# RMXU_V11.net
KiCad netlist of a schematic drawn in EAGLE
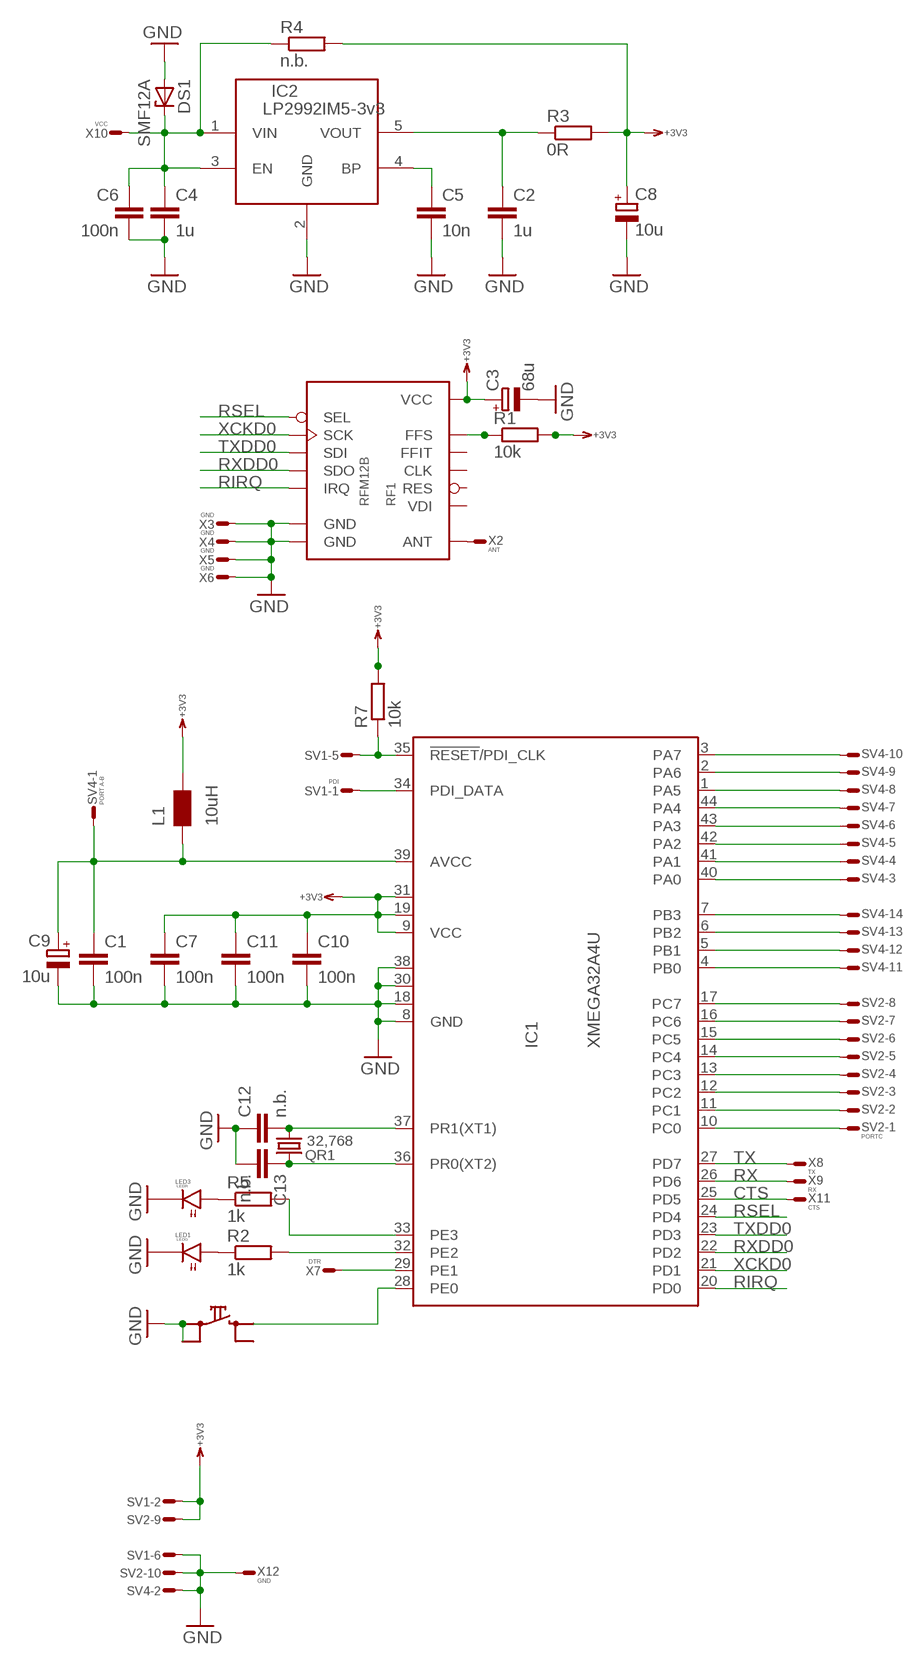
[diagram p0: schematic, sheet 1]

(export (version "E")
  (design (tool "Eeschema 10.0.6"))
  (components
    (comp (ref "C1")
      (value "100n")
      (footprint "eagle-import:0603")
      (libsource (lib "eagle-import") (part "C0603"))
    )
    (comp (ref "C2")
      (value "1u")
      (footprint "eagle-import:0603")
      (libsource (lib "eagle-import") (part "C0603"))
    )
    (comp (ref "C3")
      (value "68u")
      (footprint "eagle-import:SMC_B")
      (libsource (lib "eagle-import") (part "C_POLSMCB"))
    )
    (comp (ref "C4")
      (value "1u")
      (footprint "eagle-import:0603")
      (libsource (lib "eagle-import") (part "C0603"))
    )
    (comp (ref "C5")
      (value "10n")
      (footprint "eagle-import:0603")
      (libsource (lib "eagle-import") (part "C0603"))
    )
    (comp (ref "C6")
      (value "100n")
      (footprint "eagle-import:0603")
      (libsource (lib "eagle-import") (part "C0603"))
    )
    (comp (ref "C7")
      (value "100n")
      (footprint "eagle-import:0603")
      (libsource (lib "eagle-import") (part "C0603"))
    )
    (comp (ref "C8")
      (value "10u")
      (footprint "eagle-import:SMC_A")
      (libsource (lib "eagle-import") (part "C_POLSMCA"))
    )
    (comp (ref "C9")
      (value "10u")
      (footprint "eagle-import:SMC_A")
      (libsource (lib "eagle-import") (part "C_POLSMCA"))
    )
    (comp (ref "C10")
      (value "100n")
      (footprint "eagle-import:0603")
      (libsource (lib "eagle-import") (part "C0603"))
    )
    (comp (ref "C11")
      (value "100n")
      (footprint "eagle-import:0603")
      (libsource (lib "eagle-import") (part "C0603"))
    )
    (comp (ref "C12")
      (value "n.b.")
      (footprint "eagle-import:0603")
      (libsource (lib "eagle-import") (part "C0603"))
    )
    (comp (ref "C13")
      (value "n.b.")
      (footprint "eagle-import:0603")
      (libsource (lib "eagle-import") (part "C0603"))
    )
    (comp (ref "DS1")
      (value "SMF12A")
      (footprint "eagle-import:SMF")
      (libsource (lib "eagle-import") (part "TVS-DSMF"))
    )
    (comp (ref "IC1")
      (value "XMEGA32A4U")
      (footprint "eagle-import:TQFP44")
      (libsource (lib "eagle-import") (part "XMEGA16A4A"))
    )
    (comp (ref "IC2")
      (value "LP2992IM5-3v3")
      (footprint "eagle-import:SOT23-5")
      (libsource (lib "eagle-import") (part "LDO"))
    )
    (comp (ref "L1")
      (value "10uH")
      (footprint "eagle-import:0805")
      (libsource (lib "eagle-import") (part "L0805"))
    )
    (comp (ref "LED1")
      (value "LEDG")
      (footprint "eagle-import:1206")
      (libsource (lib "eagle-import") (part "LED1206"))
    )
    (comp (ref "LED3")
      (value "LEDR")
      (footprint "eagle-import:1206")
      (libsource (lib "eagle-import") (part "LED1206"))
    )
    (comp (ref "QR1")
      (value "32,768")
      (footprint "eagle-import:TC26H")
      (libsource (lib "eagle-import") (part "Q26H"))
    )
    (comp (ref "R1")
      (value "10k")
      (footprint "eagle-import:0603")
      (libsource (lib "eagle-import") (part "R0603"))
    )
    (comp (ref "R2")
      (value "1k")
      (footprint "eagle-import:0603")
      (libsource (lib "eagle-import") (part "R0603"))
    )
    (comp (ref "R3")
      (value "0R")
      (footprint "eagle-import:0603")
      (libsource (lib "eagle-import") (part "R0603"))
    )
    (comp (ref "R4")
      (value "n.b.")
      (footprint "eagle-import:0603")
      (libsource (lib "eagle-import") (part "R0603"))
    )
    (comp (ref "R5")
      (value "1k")
      (footprint "eagle-import:0603")
      (libsource (lib "eagle-import") (part "R0603"))
    )
    (comp (ref "R7")
      (value "10k")
      (footprint "eagle-import:0603")
      (libsource (lib "eagle-import") (part "R0603"))
    )
    (comp (ref "RF1")
      (value "RFM12B")
      (footprint "eagle-import:RFM12B")
      (libsource (lib "eagle-import") (part "RFM12BS1-868-"))
    )
    (comp (ref "SV1")
      (value "PDI")
      (footprint "eagle-import:ML6")
      (libsource (lib "eagle-import") (part "ML6E"))
    )
    (comp (ref "SV2")
      (value "PORTC")
      (footprint "eagle-import:ML10")
      (libsource (lib "eagle-import") (part "ML10?E"))
    )
    (comp (ref "SV4")
      (value "PORT A-B")
      (footprint "eagle-import:ML14")
      (libsource (lib "eagle-import") (part "ML14?E"))
    )
    (comp (ref "SW1")
      (value "SW1")
      (footprint "eagle-import:SPNO")
      (libsource (lib "eagle-import") (part "SPNO"))
    )
    (comp (ref "X2")
      (value "ANT")
      (footprint "eagle-import:T2.0_1.2")
      (libsource (lib "eagle-import") (part "WIREPADT2.0/1.2"))
    )
    (comp (ref "X3")
      (value "GND")
      (footprint "eagle-import:T2.3_1.5")
      (libsource (lib "eagle-import") (part "WIREPADT2.3/1.5"))
    )
    (comp (ref "X4")
      (value "GND")
      (footprint "eagle-import:T2.3_1.5")
      (libsource (lib "eagle-import") (part "WIREPADT2.3/1.5"))
    )
    (comp (ref "X5")
      (value "GND")
      (footprint "eagle-import:T2.3_1.5")
      (libsource (lib "eagle-import") (part "WIREPADT2.3/1.5"))
    )
    (comp (ref "X6")
      (value "GND")
      (footprint "eagle-import:T2.3_1.5")
      (libsource (lib "eagle-import") (part "WIREPADT2.3/1.5"))
    )
    (comp (ref "X7")
      (value "DTR")
      (footprint "eagle-import:T1.4_0.7L")
      (libsource (lib "eagle-import") (part "WIREPADT1.4/0.7L"))
    )
    (comp (ref "X8")
      (value "TX")
      (footprint "eagle-import:T1.4_0.7L")
      (libsource (lib "eagle-import") (part "WIREPADT1.4/0.7L"))
    )
    (comp (ref "X9")
      (value "RX")
      (footprint "eagle-import:T1.4_0.7L")
      (libsource (lib "eagle-import") (part "WIREPADT1.4/0.7L"))
    )
    (comp (ref "X10")
      (value "VCC")
      (footprint "eagle-import:T1.4_0.7L")
      (libsource (lib "eagle-import") (part "WIREPADT1.4/0.7L"))
    )
    (comp (ref "X11")
      (value "CTS")
      (footprint "eagle-import:T1.4_0.7L")
      (libsource (lib "eagle-import") (part "WIREPADT1.4/0.7L"))
    )
    (comp (ref "X12")
      (value "GND")
      (footprint "eagle-import:T1.4_0.7L")
      (libsource (lib "eagle-import") (part "WIREPADT1.4/0.7L"))
    )
  )
  (nets
    (net (code "1") (name "+3V3") (class "Default")
      (node (ref "C10") (pin "1") (pinfunction "1_1") (pintype "passive"))
      (node (ref "C11") (pin "1") (pinfunction "1_1") (pintype "passive"))
      (node (ref "C3") (pin "+") (pinfunction "+_+") (pintype "passive"))
      (node (ref "C7") (pin "1") (pinfunction "1_1") (pintype "passive"))
      (node (ref "C8") (pin "+") (pinfunction "+_+") (pintype "passive"))
      (node (ref "IC1") (pin "19") (pinfunction "VCC1_19") (pintype "bidirectional"))
      (node (ref "IC1") (pin "31") (pinfunction "VCC2_31") (pintype "bidirectional"))
      (node (ref "IC1") (pin "9") (pinfunction "VCC_9") (pintype "bidirectional"))
      (node (ref "L1") (pin "2") (pinfunction "2_2") (pintype "passive"))
      (node (ref "R1") (pin "2") (pinfunction "2_2") (pintype "passive"))
      (node (ref "R3") (pin "2") (pinfunction "2_2") (pintype "passive"))
      (node (ref "R4") (pin "2") (pinfunction "2_2") (pintype "passive"))
      (node (ref "R7") (pin "2") (pinfunction "2_2") (pintype "passive"))
      (node (ref "RF1") (pin "VDD") (pinfunction "VCC_VDD") (pintype "power_in"))
      (node (ref "SV1") (pin "2") (pinfunction "S_2") (pintype "passive"))
      (node (ref "SV2") (pin "9") (pinfunction "S_9") (pintype "passive"))
    )
    (net (code "2") (name "/CTS") (class "Default")
      (node (ref "IC1") (pin "25") (pinfunction "PD5_25") (pintype "bidirectional"))
      (node (ref "X11") (pin "1") (pinfunction "S_1") (pintype "passive"))
    )
    (net (code "3") (name "/RIRQ") (class "Default")
      (node (ref "IC1") (pin "20") (pinfunction "PD0_20") (pintype "bidirectional"))
      (node (ref "RF1") (pin "IRQ") (pinfunction "IRQ_IRQ") (pintype "open_collector"))
    )
    (net (code "4") (name "/RSEL") (class "Default")
      (node (ref "IC1") (pin "24") (pinfunction "PD4_24") (pintype "bidirectional"))
      (node (ref "RF1") (pin "SEL") (pinfunction "SEL_SEL") (pintype "input"))
    )
    (net (code "5") (name "/RX") (class "Default")
      (node (ref "IC1") (pin "26") (pinfunction "PD6_26") (pintype "bidirectional"))
      (node (ref "X9") (pin "1") (pinfunction "S_1") (pintype "passive"))
    )
    (net (code "6") (name "/RXDD0") (class "Default")
      (node (ref "IC1") (pin "22") (pinfunction "PD2_22") (pintype "bidirectional"))
      (node (ref "RF1") (pin "SDO") (pinfunction "SDO_SDO") (pintype "output"))
    )
    (net (code "7") (name "/TX") (class "Default")
      (node (ref "IC1") (pin "27") (pinfunction "PD7_27") (pintype "bidirectional"))
      (node (ref "X8") (pin "1") (pinfunction "S_1") (pintype "passive"))
    )
    (net (code "8") (name "/TXDD0") (class "Default")
      (node (ref "IC1") (pin "23") (pinfunction "PD3_23") (pintype "bidirectional"))
      (node (ref "RF1") (pin "SDI") (pinfunction "SDI_SDI") (pintype "input"))
    )
    (net (code "9") (name "/XCKD0") (class "Default")
      (node (ref "IC1") (pin "21") (pinfunction "PD1_21") (pintype "bidirectional"))
      (node (ref "RF1") (pin "SCK") (pinfunction "SCK_SCK") (pintype "input"))
    )
    (net (code "10") (name "GND") (class "Default")
      (node (ref "C1") (pin "2") (pinfunction "2_2") (pintype "passive"))
      (node (ref "C10") (pin "2") (pinfunction "2_2") (pintype "passive"))
      (node (ref "C11") (pin "2") (pinfunction "2_2") (pintype "passive"))
      (node (ref "C12") (pin "1") (pinfunction "1_1") (pintype "passive"))
      (node (ref "C13") (pin "2") (pinfunction "2_2") (pintype "passive"))
      (node (ref "C2") (pin "2") (pinfunction "2_2") (pintype "passive"))
      (node (ref "C3") (pin "-") (pinfunction "-_-") (pintype "passive"))
      (node (ref "C4") (pin "2") (pinfunction "2_2") (pintype "passive"))
      (node (ref "C5") (pin "2") (pinfunction "2_2") (pintype "passive"))
      (node (ref "C6") (pin "2") (pinfunction "2_2") (pintype "passive"))
      (node (ref "C7") (pin "2") (pinfunction "2_2") (pintype "passive"))
      (node (ref "C8") (pin "-") (pinfunction "-_-") (pintype "passive"))
      (node (ref "C9") (pin "-") (pinfunction "-_-") (pintype "passive"))
      (node (ref "DS1") (pin "A") (pinfunction "A_A") (pintype "passive"))
      (node (ref "IC1") (pin "18") (pinfunction "GND1_18") (pintype "bidirectional"))
      (node (ref "IC1") (pin "30") (pinfunction "GND2_30") (pintype "bidirectional"))
      (node (ref "IC1") (pin "38") (pinfunction "GND3_38") (pintype "bidirectional"))
      (node (ref "IC1") (pin "8") (pinfunction "GND_8") (pintype "bidirectional"))
      (node (ref "IC2") (pin "2") (pinfunction "GND_2") (pintype "bidirectional"))
      (node (ref "LED1") (pin "2") (pinfunction "C_2") (pintype "bidirectional"))
      (node (ref "LED3") (pin "2") (pinfunction "C_2") (pintype "bidirectional"))
      (node (ref "RF1") (pin "GND") (pinfunction "GND_GND") (pintype "power_in"))
      (node (ref "RF1") (pin "GND@1") (pinfunction "GND_GND@1") (pintype "power_in"))
      (node (ref "SV1") (pin "6") (pinfunction "S_6") (pintype "passive"))
      (node (ref "SV2") (pin "10") (pinfunction "S_10") (pintype "passive"))
      (node (ref "SV4") (pin "2") (pinfunction "S_2") (pintype "passive"))
      (node (ref "SW1") (pin "1") (pinfunction "1.1_1") (pintype "bidirectional"))
      (node (ref "SW1") (pin "2") (pinfunction "1.2_2") (pintype "bidirectional"))
      (node (ref "X12") (pin "1") (pinfunction "S_1") (pintype "passive"))
      (node (ref "X3") (pin "P$1") (pinfunction "S_P$1") (pintype "passive"))
      (node (ref "X4") (pin "P$1") (pinfunction "S_P$1") (pintype "passive"))
      (node (ref "X5") (pin "P$1") (pinfunction "S_P$1") (pintype "passive"))
      (node (ref "X6") (pin "P$1") (pinfunction "S_P$1") (pintype "passive"))
    )
    (net (code "11") (name "Net-(IC1-AVCC)") (class "Default")
      (node (ref "C1") (pin "1") (pinfunction "1_1") (pintype "passive"))
      (node (ref "C9") (pin "+") (pinfunction "+_+") (pintype "passive"))
      (node (ref "IC1") (pin "39") (pinfunction "AVCC_39") (pintype "bidirectional"))
      (node (ref "L1") (pin "1") (pinfunction "1_1") (pintype "passive"))
      (node (ref "SV4") (pin "1") (pinfunction "S_1") (pintype "passive"))
    )
    (net (code "12") (name "Net-(IC1-PA0)") (class "Default")
      (node (ref "IC1") (pin "40") (pinfunction "PA0_40") (pintype "bidirectional"))
      (node (ref "SV4") (pin "3") (pinfunction "S_3") (pintype "passive"))
    )
    (net (code "13") (name "Net-(IC1-PA1)") (class "Default")
      (node (ref "IC1") (pin "41") (pinfunction "PA1_41") (pintype "bidirectional"))
      (node (ref "SV4") (pin "4") (pinfunction "S_4") (pintype "passive"))
    )
    (net (code "14") (name "Net-(IC1-PA2)") (class "Default")
      (node (ref "IC1") (pin "42") (pinfunction "PA2_42") (pintype "bidirectional"))
      (node (ref "SV4") (pin "5") (pinfunction "S_5") (pintype "passive"))
    )
    (net (code "15") (name "Net-(IC1-PA3)") (class "Default")
      (node (ref "IC1") (pin "43") (pinfunction "PA3_43") (pintype "bidirectional"))
      (node (ref "SV4") (pin "6") (pinfunction "S_6") (pintype "passive"))
    )
    (net (code "16") (name "Net-(IC1-PA4)") (class "Default")
      (node (ref "IC1") (pin "44") (pinfunction "PA4_44") (pintype "bidirectional"))
      (node (ref "SV4") (pin "7") (pinfunction "S_7") (pintype "passive"))
    )
    (net (code "17") (name "Net-(IC1-PA5)") (class "Default")
      (node (ref "IC1") (pin "1") (pinfunction "PA5_1") (pintype "bidirectional"))
      (node (ref "SV4") (pin "8") (pinfunction "S_8") (pintype "passive"))
    )
    (net (code "18") (name "Net-(IC1-PA6)") (class "Default")
      (node (ref "IC1") (pin "2") (pinfunction "PA6_2") (pintype "bidirectional"))
      (node (ref "SV4") (pin "9") (pinfunction "S_9") (pintype "passive"))
    )
    (net (code "19") (name "Net-(IC1-PA7)") (class "Default")
      (node (ref "IC1") (pin "3") (pinfunction "PA7_3") (pintype "bidirectional"))
      (node (ref "SV4") (pin "10") (pinfunction "S_10") (pintype "passive"))
    )
    (net (code "20") (name "Net-(IC1-PB0)") (class "Default")
      (node (ref "IC1") (pin "4") (pinfunction "PB0_4") (pintype "bidirectional"))
      (node (ref "SV4") (pin "11") (pinfunction "S_11") (pintype "passive"))
    )
    (net (code "21") (name "Net-(IC1-PB1)") (class "Default")
      (node (ref "IC1") (pin "5") (pinfunction "PB1_5") (pintype "bidirectional"))
      (node (ref "SV4") (pin "12") (pinfunction "S_12") (pintype "passive"))
    )
    (net (code "22") (name "Net-(IC1-PB2)") (class "Default")
      (node (ref "IC1") (pin "6") (pinfunction "PB2_6") (pintype "bidirectional"))
      (node (ref "SV4") (pin "13") (pinfunction "S_13") (pintype "passive"))
    )
    (net (code "23") (name "Net-(IC1-PB3)") (class "Default")
      (node (ref "IC1") (pin "7") (pinfunction "PB3_7") (pintype "bidirectional"))
      (node (ref "SV4") (pin "14") (pinfunction "S_14") (pintype "passive"))
    )
    (net (code "24") (name "Net-(IC1-PC0)") (class "Default")
      (node (ref "IC1") (pin "10") (pinfunction "PC0_10") (pintype "bidirectional"))
      (node (ref "SV2") (pin "1") (pinfunction "S_1") (pintype "passive"))
    )
    (net (code "25") (name "Net-(IC1-PC1)") (class "Default")
      (node (ref "IC1") (pin "11") (pinfunction "PC1_11") (pintype "bidirectional"))
      (node (ref "SV2") (pin "2") (pinfunction "S_2") (pintype "passive"))
    )
    (net (code "26") (name "Net-(IC1-PC2)") (class "Default")
      (node (ref "IC1") (pin "12") (pinfunction "PC2_12") (pintype "bidirectional"))
      (node (ref "SV2") (pin "3") (pinfunction "S_3") (pintype "passive"))
    )
    (net (code "27") (name "Net-(IC1-PC3)") (class "Default")
      (node (ref "IC1") (pin "13") (pinfunction "PC3_13") (pintype "bidirectional"))
      (node (ref "SV2") (pin "4") (pinfunction "S_4") (pintype "passive"))
    )
    (net (code "28") (name "Net-(IC1-PC4)") (class "Default")
      (node (ref "IC1") (pin "14") (pinfunction "PC4_14") (pintype "bidirectional"))
      (node (ref "SV2") (pin "5") (pinfunction "S_5") (pintype "passive"))
    )
    (net (code "29") (name "Net-(IC1-PC5)") (class "Default")
      (node (ref "IC1") (pin "15") (pinfunction "PC5_15") (pintype "bidirectional"))
      (node (ref "SV2") (pin "6") (pinfunction "S_6") (pintype "passive"))
    )
    (net (code "30") (name "Net-(IC1-PC6)") (class "Default")
      (node (ref "IC1") (pin "16") (pinfunction "PC6_16") (pintype "bidirectional"))
      (node (ref "SV2") (pin "7") (pinfunction "S_7") (pintype "passive"))
    )
    (net (code "31") (name "Net-(IC1-PC7)") (class "Default")
      (node (ref "IC1") (pin "17") (pinfunction "PC7_17") (pintype "bidirectional"))
      (node (ref "SV2") (pin "8") (pinfunction "S_8") (pintype "passive"))
    )
    (net (code "32") (name "Net-(IC1-PDI_DATA)") (class "Default")
      (node (ref "IC1") (pin "34") (pinfunction "PDI_DATA_34") (pintype "bidirectional"))
      (node (ref "SV1") (pin "1") (pinfunction "S_1") (pintype "passive"))
    )
    (net (code "33") (name "Net-(IC1-PE0)") (class "Default")
      (node (ref "IC1") (pin "28") (pinfunction "PE0_28") (pintype "bidirectional"))
      (node (ref "SW1") (pin "3") (pinfunction "2.1_3") (pintype "bidirectional"))
    )
    (net (code "34") (name "Net-(IC1-PE1)") (class "Default")
      (node (ref "IC1") (pin "29") (pinfunction "PE1_29") (pintype "bidirectional"))
      (node (ref "X7") (pin "1") (pinfunction "S_1") (pintype "passive"))
    )
    (net (code "35") (name "Net-(IC1-PE2)") (class "Default")
      (node (ref "IC1") (pin "32") (pinfunction "PE2_32") (pintype "bidirectional"))
      (node (ref "R2") (pin "2") (pinfunction "2_2") (pintype "passive"))
    )
    (net (code "36") (name "Net-(IC1-PE3)") (class "Default")
      (node (ref "IC1") (pin "33") (pinfunction "PE3_33") (pintype "bidirectional"))
      (node (ref "R5") (pin "2") (pinfunction "2_2") (pintype "passive"))
    )
    (net (code "37") (name "Net-(IC1-PR0(XT2))") (class "Default")
      (node (ref "C13") (pin "1") (pinfunction "1_1") (pintype "passive"))
      (node (ref "IC1") (pin "36") (pinfunction "PR0(XT2)_36") (pintype "bidirectional"))
      (node (ref "QR1") (pin "2") (pinfunction "2_2") (pintype "passive"))
    )
    (net (code "38") (name "Net-(IC1-PR1(XT1))") (class "Default")
      (node (ref "C12") (pin "2") (pinfunction "2_2") (pintype "passive"))
      (node (ref "IC1") (pin "37") (pinfunction "PR1(XT1)_37") (pintype "bidirectional"))
      (node (ref "QR1") (pin "1") (pinfunction "1_1") (pintype "passive"))
    )
    (net (code "39") (name "Net-(IC1-~{RESET}{slash}PDI_CLK)") (class "Default")
      (node (ref "IC1") (pin "35") (pinfunction "~{RESET}/PDI_CLK_35") (pintype "bidirectional"))
      (node (ref "R7") (pin "1") (pinfunction "1_1") (pintype "passive"))
      (node (ref "SV1") (pin "5") (pinfunction "S_5") (pintype "passive"))
    )
    (net (code "40") (name "Net-(IC2-BP)") (class "Default")
      (node (ref "C5") (pin "1") (pinfunction "1_1") (pintype "passive"))
      (node (ref "IC2") (pin "4") (pinfunction "BP_4") (pintype "bidirectional"))
    )
    (net (code "41") (name "Net-(IC2-EN)") (class "Default")
      (node (ref "C4") (pin "1") (pinfunction "1_1") (pintype "passive"))
      (node (ref "C6") (pin "1") (pinfunction "1_1") (pintype "passive"))
      (node (ref "DS1") (pin "C") (pinfunction "C_C") (pintype "passive"))
      (node (ref "IC2") (pin "1") (pinfunction "VIN_1") (pintype "bidirectional"))
      (node (ref "IC2") (pin "3") (pinfunction "EN_3") (pintype "bidirectional"))
      (node (ref "R4") (pin "1") (pinfunction "1_1") (pintype "passive"))
      (node (ref "X10") (pin "1") (pinfunction "S_1") (pintype "passive"))
    )
    (net (code "42") (name "Net-(IC2-VOUT)") (class "Default")
      (node (ref "C2") (pin "1") (pinfunction "1_1") (pintype "passive"))
      (node (ref "IC2") (pin "5") (pinfunction "VOUT_5") (pintype "bidirectional"))
      (node (ref "R3") (pin "1") (pinfunction "1_1") (pintype "passive"))
    )
    (net (code "43") (name "Net-(LED1-A)") (class "Default")
      (node (ref "LED1") (pin "1") (pinfunction "A_1") (pintype "bidirectional"))
      (node (ref "R2") (pin "1") (pinfunction "1_1") (pintype "passive"))
    )
    (net (code "44") (name "Net-(LED3-A)") (class "Default")
      (node (ref "LED3") (pin "1") (pinfunction "A_1") (pintype "bidirectional"))
      (node (ref "R5") (pin "1") (pinfunction "1_1") (pintype "passive"))
    )
    (net (code "45") (name "Net-(R1-Pad1)") (class "Default")
      (node (ref "R1") (pin "1") (pinfunction "1_1") (pintype "passive"))
      (node (ref "RF1") (pin "FFS") (pinfunction "FFS_FFS") (pintype "bidirectional"))
    )
    (net (code "46") (name "Net-(X2-S)") (class "Default")
      (node (ref "RF1") (pin "ANT") (pinfunction "ANT_ANT") (pintype "passive"))
      (node (ref "X2") (pin "P$1") (pinfunction "S_P$1") (pintype "passive"))
    )
    (net (code "47") (name "unconnected-(RF1-FFIT-PadCFIL)") (class "Default")
      (node (ref "RF1") (pin "CFIL") (pinfunction "FFIT_CFIL") (pintype "bidirectional"))
    )
    (net (code "48") (name "unconnected-(RF1-PadCLK)") (class "Default")
      (node (ref "RF1") (pin "CLK") (pinfunction "CLK_CLK") (pintype "output"))
    )
    (net (code "49") (name "unconnected-(RF1-RES-Pad{slash}RES)") (class "Default")
      (node (ref "RF1") (pin "/RES") (pinfunction "RES_/RES") (pintype "bidirectional"))
    )
    (net (code "50") (name "unconnected-(RF1-VDI-PadINT)") (class "Default")
      (node (ref "RF1") (pin "INT") (pinfunction "VDI_INT") (pintype "bidirectional"))
    )
    (net (code "51") (name "unconnected-(SW1-2.2-Pad4)") (class "Default")
      (node (ref "SW1") (pin "4") (pinfunction "2.2_4") (pintype "bidirectional"))
    )
  )
)
